# Signal_RX.net
KiCad netlist of a schematic drawn in Altium Designer
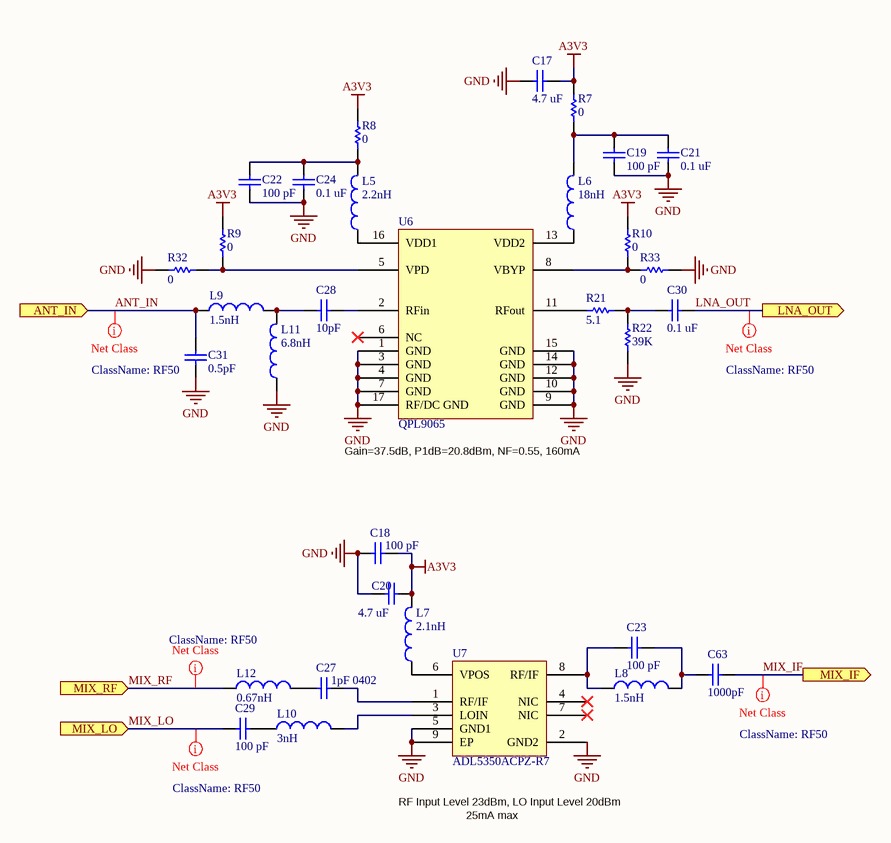
[diagram p0: Signal_RX.SchDoc]

(export (version "E")
  (design (tool "Eeschema 10.0.6"))
  (components
    (comp (ref "C17")
      (value "4.7 uF")
      (footprint "CAPC1608X10L")
      (description "Multilayer Ceramic Capacitors MLCC - SMD/SMT 0603 4.7uF 16volts X5R + - 10%")
      (fields
        (field (name "MANUFACTURER") "Murata Electronics")
        (field (name "MANUFACTURER PART NUMBER") "GRM188R61C475KAAJD")
      )
      (libsource (lib "Componentes_base") (part "GRM188R61C475KAAJD_1"))
    )
    (comp (ref "C18")
      (value "100 pF")
      (footprint "CAPC1005X05L")
      (description "CAP CER 100PF 50V NP0 0402")
      (fields
        (field (name "MANUFACTURER") "Murata Electronics North America")
        (field (name "MANUFACTURER PART NUMBER") "GRM1555C1H101GA01D")
      )
      (libsource (lib "Componentes_base") (part "GRM1555C1H101GA01D"))
    )
    (comp (ref "C19")
      (value "100 pF")
      (footprint "CAPC1005X05L")
      (description "CAP CER 100PF 50V NP0 0402")
      (fields
        (field (name "MANUFACTURER") "Murata Electronics North America")
        (field (name "MANUFACTURER PART NUMBER") "GRM1555C1H101GA01D")
      )
      (libsource (lib "Componentes_base") (part "GRM1555C1H101GA01D"))
    )
    (comp (ref "C20")
      (value "4.7 uF")
      (footprint "CAPC1608X10L")
      (description "Multilayer Ceramic Capacitors MLCC - SMD/SMT 0603 4.7uF 16volts X5R + - 10%")
      (fields
        (field (name "MANUFACTURER") "Murata Electronics")
        (field (name "MANUFACTURER PART NUMBER") "GRM188R61C475KAAJD")
      )
      (libsource (lib "Componentes_base") (part "GRM188R61C475KAAJD"))
    )
    (comp (ref "C21")
      (value "0.1 uF")
      (footprint "CAPC1005X05L")
      (description "CAP CER 0.1UF 16V 10% X7R 0402")
      (fields
        (field (name "MANUFACTURER") "Samsung Electro-Mechanics America, Inc")
        (field (name "MANUFACTURER PART NUMBER") "CL05B104KO5NNNC")
      )
      (libsource (lib "Componentes_base") (part "CL05B104KO5NNNC"))
    )
    (comp (ref "C22")
      (value "100 pF")
      (footprint "CAPC1005X05L")
      (description "CAP CER 100PF 50V NP0 0402")
      (fields
        (field (name "MANUFACTURER") "Murata Electronics North America")
        (field (name "MANUFACTURER PART NUMBER") "GRM1555C1H101GA01D")
      )
      (libsource (lib "Componentes_base") (part "GRM1555C1H101GA01D"))
    )
    (comp (ref "C23")
      (value "100 pF")
      (footprint "CAPC1005X05L")
      (description "CAP CER 100PF 50V NP0 0402")
      (fields
        (field (name "MANUFACTURER") "Murata Electronics North America")
        (field (name "MANUFACTURER PART NUMBER") "GRM1555C1H101GA01D")
      )
      (libsource (lib "Componentes_base") (part "GRM1555C1H101GA01D"))
    )
    (comp (ref "C24")
      (value "0.1 uF")
      (footprint "CAPC1005X05L")
      (description "CAP CER 0.1UF 16V 10% X7R 0402")
      (fields
        (field (name "MANUFACTURER") "Samsung Electro-Mechanics America, Inc")
        (field (name "MANUFACTURER PART NUMBER") "CL05B104KO5NNNC")
      )
      (libsource (lib "Componentes_base") (part "CL05B104KO5NNNC"))
    )
    (comp (ref "C27")
      (value "1pF 0402")
      (footprint "CAPC1005X05L")
      (description "CAP CER 1PF 50V C0G/NP0 0402")
      (libsource (lib "Componentes_base") (part "GRM1555C1H1R0CA01D"))
    )
    (comp (ref "C28")
      (value "10pF")
      (footprint "CAPC1005X05L")
      (description "CAP CER 10PF 50V C0G/NP0 0402")
      (fields
        (field (name "MANUFACTURER") "Murata Electronics North America")
        (field (name "MANUFACTURER PART NUMBER") "GRM1555C1H100JA01D")
      )
      (libsource (lib "Componentes_base") (part "GRM1555C1H100JA01D"))
    )
    (comp (ref "C29")
      (value "100 pF")
      (footprint "CAPC1005X05L")
      (description "CAP CER 100PF 50V NP0 0402")
      (fields
        (field (name "MANUFACTURER") "Murata Electronics North America")
        (field (name "MANUFACTURER PART NUMBER") "GRM1555C1H101GA01D")
      )
      (libsource (lib "Componentes_base") (part "GRM1555C1H101GA01D"))
    )
    (comp (ref "C30")
      (value "0.1 uF")
      (footprint "CAPC1005X05L")
      (description "CAP CER 0.1UF 16V 10% X7R 0402")
      (fields
        (field (name "MANUFACTURER") "Samsung Electro-Mechanics America, Inc")
        (field (name "MANUFACTURER PART NUMBER") "CL05B104KO5NNNC")
      )
      (libsource (lib "Componentes_base") (part "CL05B104KO5NNNC"))
    )
    (comp (ref "C31")
      (value "0.5pF")
      (footprint "CAPC1005X05L")
      (description "CAP CER 0.5PF 50V C0G/NP0 0402")
      (fields
        (field (name "MANUFACTURER") "Murata Electronics North America")
        (field (name "MANUFACTURER PART NUMBER") "GJM1555C1HR50BB01D")
      )
      (libsource (lib "Componentes_base") (part "GJM1555C1HR50BB01D"))
    )
    (comp (ref "C63")
      (value "1000pF")
      (footprint "CAPC1005X05L")
      (description "CAP CER 1000PF 50V C0G/NP0 0402")
      (fields
        (field (name "MANUFACTURER") "Murata Electronics North America")
        (field (name "MANUFACTURER PART NUMBER") "GRM1555C1H102JA01D")
      )
      (libsource (lib "Componentes_base") (part "GRM1555C1H102JA01D"))
    )
    (comp (ref "L5")
      (value "2.2nH")
      (footprint "INDC1005X06L")
      (description "FIXED IND 2.2NH 1A 27 MOHM SMD")
      (fields
        (field (name "MANUFACTURER") "Murata Electronics North America")
        (field (name "MANUFACTURER PART NUMBER") "LQW15AN2N2C10D")
      )
      (libsource (lib "Componentes_base") (part "LQW15AN2N2C10D"))
    )
    (comp (ref "L6")
      (value "18nH")
      (footprint "INDC1811X10L 0603CS")
      (description "COILCRAFT - 0603CS-18NXJLU - INDUCTOR, RF, 18NH, 5%, 3.1GHZ, SMD")
      (libsource (lib "Componentes_base") (part "0603CS-18NXJLU"))
    )
    (comp (ref "L7")
      (value "2.1nH")
      (footprint "INDC0905X05N-0302CS")
      (description "COILCRAFT - 0302CS-2N1XJLU - INDUCTOR, RF, 2.1NH,5%,15.94GHZ, SMD")
      (fields
        (field (name "MANUFACTURER") "COILCRAFT")
        (field (name "MANUFACTURER PART NUMBER") "0302CS-2N1XJLU")
        (field (name "FRECUENCIA AUTORRESONANTE MÍN.") "5.94")
      )
      (libsource (lib "Componentes_base") (part "0302CS-2N1XJLU"))
    )
    (comp (ref "L8")
      (value "1.5nH")
      (footprint "INDC1005X06L")
      (description "FIXED IND 1.5NH 280MA 200 MOHM")
      (fields
        (field (name "MANUFACTURER") "Murata Electronics North America")
        (field (name "MANUFACTURER PART NUMBER") "LQP15MN1N5B02D")
      )
      (libsource (lib "Componentes_base") (part "LQP15MN1N5B02D"))
    )
    (comp (ref "L9")
      (value "1.5nH")
      (footprint "INDC1005X06L")
      (description "FIXED IND 1.5NH 280MA 200 MOHM")
      (fields
        (field (name "MANUFACTURER") "Murata Electronics North America")
        (field (name "MANUFACTURER PART NUMBER") "LQP15MN1N5B02D")
      )
      (libsource (lib "Componentes_base") (part "LQP15MN1N5B02D"))
    )
    (comp (ref "L10")
      (value "3nH")
      (footprint "INDC1005X06L")
      (description "FIXED IND 3NH 190MA 400 MOHM SMD")
      (fields
        (field (name "MANUFACTURER") "Murata Electronics North America")
        (field (name "MANUFACTURER PART NUMBER") "LQP15MN3N0B02D")
      )
      (libsource (lib "Componentes_base") (part "LQP15MN3N0B02D"))
    )
    (comp (ref "L11")
      (value "6.8nH")
      (footprint "INDC1005X06L")
      (description "FIXED IND 6.8NH 600MA 240 MOHM")
      (fields
        (field (name "MANUFACTURER") "Murata Electronics North America")
        (field (name "MANUFACTURER PART NUMBER") "LQG15HS6N8J02D")
      )
      (libsource (lib "Componentes_base") (part "LQG15HS6N8J02D"))
    )
    (comp (ref "L12")
      (value "0.67nH")
      (footprint "INDC0905X05N-0302CS")
      (description "COILCRAFT - 0302CS-N67XKLU - INDUCTOR, RF, 0.67NH, 10%,26GHZ, SMD")
      (fields
        (field (name "MANUFACTURER") "COILCRAFT")
        (field (name "MANUFACTURER PART NUMBER") "0302CS-N67XKLU")
        (field (name "FRECUENCIA AUTORRESONANTE MÍN.") "26")
      )
      (libsource (lib "Componentes_base") (part "0302CS-N67XKLU"))
    )
    (comp (ref "R7")
      (value "0")
      (footprint "RESC1005X04L")
      (description "RES 0.0 OHM 1/16W JUMP 0402")
      (fields
        (field (name "MANUFACTURER") "Samsung Electro-Mechanics America, Inc")
        (field (name "MANUFACTURER PART NUMBER") "RC1005J000CS")
      )
      (libsource (lib "Componentes_base") (part "RC1005J000CS"))
    )
    (comp (ref "R8")
      (value "0")
      (footprint "RESC1005X04L")
      (description "RES 0.0 OHM 1/16W JUMP 0402")
      (fields
        (field (name "MANUFACTURER") "Samsung Electro-Mechanics America, Inc")
        (field (name "MANUFACTURER PART NUMBER") "RC1005J000CS")
      )
      (libsource (lib "Componentes_base") (part "RC1005J000CS"))
    )
    (comp (ref "R9")
      (value "0")
      (footprint "RESC1005X04L")
      (description "RES 0.0 OHM 1/16W JUMP 0402")
      (fields
        (field (name "MANUFACTURER") "Samsung Electro-Mechanics America, Inc")
        (field (name "MANUFACTURER PART NUMBER") "RC1005J000CS")
      )
      (libsource (lib "Componentes_base") (part "RC1005J000CS"))
    )
    (comp (ref "R10")
      (value "0")
      (footprint "RESC1005X04L")
      (description "RES 0.0 OHM 1/16W JUMP 0402")
      (fields
        (field (name "MANUFACTURER") "Samsung Electro-Mechanics America, Inc")
        (field (name "MANUFACTURER PART NUMBER") "RC1005J000CS")
      )
      (libsource (lib "Componentes_base") (part "RC1005J000CS"))
    )
    (comp (ref "R21")
      (value "5.1")
      (footprint "RESC1005X04L")
      (description "RES SMD 5.1 OHM 1% 1/16W 0402")
      (fields
        (field (name "MANUFACTURER") "Samsung Electro-Mechanics America, Inc.")
        (field (name "MANUFACTURER PART NUMBER") "RC1005F5R1CS")
      )
      (libsource (lib "Componentes_base") (part "RC1005F5R1CS"))
    )
    (comp (ref "R22")
      (value "39K")
      (footprint "RESC1005X04L")
      (description "RES SMD 39K OHM 1% 1/16W 0402")
      (fields
        (field (name "MANUFACTURER") "Yageo")
        (field (name "MANUFACTURER PART NUMBER") "RC0402FR-0739KL")
      )
      (libsource (lib "Componentes_base") (part "RC0402FR-0739KL"))
    )
    (comp (ref "R32")
      (value "0")
      (footprint "RESC1005X04L")
      (description "RES 0.0 OHM 1/16W JUMP 0402")
      (fields
        (field (name "MANUFACTURER") "Samsung Electro-Mechanics America, Inc")
        (field (name "MANUFACTURER PART NUMBER") "RC1005J000CS")
      )
      (libsource (lib "Componentes_base") (part "RC1005J000CS"))
    )
    (comp (ref "R33")
      (value "0")
      (footprint "RESC1005X04L")
      (description "RES 0.0 OHM 1/16W JUMP 0402")
      (fields
        (field (name "MANUFACTURER") "Samsung Electro-Mechanics America, Inc")
        (field (name "MANUFACTURER PART NUMBER") "RC1005J000CS")
      )
      (libsource (lib "Componentes_base") (part "RC1005J000CS"))
    )
    (comp (ref "U6")
      (value "QPL9065")
      (footprint "QFN50P350X350X86_HS-17N-qorvo")
      (fields
        (field (name "MANUFACTURER PART NUMBER") "772-QPL9065TR13")
        (field (name "MANUFACTURER") "COILCRAFT")
        (field (name "FRECUENCIA AUTORRESONANTE MÍN.") "3.1")
      )
      (libsource (lib "Componentes_base") (part "QPL9065"))
    )
    (comp (ref "U7")
      (value "ADL5350ACPZ-R7")
      (footprint "SON50P200X80_HS-9N")
      (description "IC MIXER 750MHZ-4GHZ 8LFCSP")
      (fields (field (name "MANUFACTURER") "Analog Devices Inc."))
      (libsource (lib "Componentes_base") (part "ADL5350ACPZ-R7"))
    )
  )
  (nets
    (net (code "1") (name "/ANT_IN") (class "Default")
      (node (ref "C31") (pin "2") (pinfunction "2_2") (pintype "passive"))
      (node (ref "L9") (pin "1") (pinfunction "1_1") (pintype "passive"))
    )
    (net (code "2") (name "/LNA_OUT") (class "Default")
      (node (ref "C30") (pin "1") (pinfunction "1_1") (pintype "passive"))
    )
    (net (code "3") (name "/MIX_IF") (class "Default")
      (node (ref "C63") (pin "2") (pinfunction "2_2") (pintype "passive"))
    )
    (net (code "4") (name "/MIX_LO") (class "Default")
      (node (ref "C29") (pin "1") (pinfunction "1_1") (pintype "passive"))
    )
    (net (code "5") (name "/MIX_RF") (class "Default")
      (node (ref "L12") (pin "1") (pinfunction "1_1") (pintype "passive"))
    )
    (net (code "6") (name "A3V3") (class "Default")
      (node (ref "C17") (pin "2") (pinfunction "2_2") (pintype "passive"))
      (node (ref "C18") (pin "2") (pinfunction "2_2") (pintype "passive"))
      (node (ref "C20") (pin "1") (pinfunction "1_1") (pintype "passive"))
      (node (ref "L7") (pin "2") (pinfunction "2_2") (pintype "passive"))
      (node (ref "R10") (pin "1") (pinfunction "1_1") (pintype "passive"))
      (node (ref "R7") (pin "2") (pinfunction "2_2") (pintype "passive"))
      (node (ref "R8") (pin "1") (pinfunction "1_1") (pintype "passive"))
      (node (ref "R9") (pin "2") (pinfunction "2_2") (pintype "passive"))
    )
    (net (code "7") (name "GND") (class "Default")
      (node (ref "C17") (pin "1") (pinfunction "1_1") (pintype "passive"))
      (node (ref "C18") (pin "1") (pinfunction "1_1") (pintype "passive"))
      (node (ref "C19") (pin "2") (pinfunction "2_2") (pintype "passive"))
      (node (ref "C20") (pin "2") (pinfunction "2_2") (pintype "passive"))
      (node (ref "C21") (pin "1") (pinfunction "1_1") (pintype "passive"))
      (node (ref "C22") (pin "2") (pinfunction "2_2") (pintype "passive"))
      (node (ref "C24") (pin "1") (pinfunction "1_1") (pintype "passive"))
      (node (ref "C31") (pin "1") (pinfunction "1_1") (pintype "passive"))
      (node (ref "L11") (pin "1") (pinfunction "1_1") (pintype "passive"))
      (node (ref "R22") (pin "1") (pinfunction "1_1") (pintype "passive"))
      (node (ref "R32") (pin "2") (pinfunction "2_2") (pintype "passive"))
      (node (ref "R33") (pin "1") (pinfunction "1_1") (pintype "passive"))
      (node (ref "U6") (pin "1") (pinfunction "GND_1") (pintype "passive"))
      (node (ref "U6") (pin "10") (pinfunction "GND_10") (pintype "passive"))
      (node (ref "U6") (pin "12") (pinfunction "GND_12") (pintype "passive"))
      (node (ref "U6") (pin "14") (pinfunction "GND_14") (pintype "passive"))
      (node (ref "U6") (pin "15") (pinfunction "GND_15") (pintype "passive"))
      (node (ref "U6") (pin "17") (pinfunction "RF/DC_GND_17") (pintype "passive"))
      (node (ref "U6") (pin "3") (pinfunction "GND_3") (pintype "passive"))
      (node (ref "U6") (pin "4") (pinfunction "GND_4") (pintype "passive"))
      (node (ref "U6") (pin "7") (pinfunction "GND_7") (pintype "passive"))
      (node (ref "U6") (pin "9") (pinfunction "GND_9") (pintype "passive"))
      (node (ref "U7") (pin "2") (pinfunction "GND2_2") (pintype "passive"))
      (node (ref "U7") (pin "5") (pinfunction "GND1_5") (pintype "passive"))
      (node (ref "U7") (pin "9") (pinfunction "EP_9") (pintype "passive"))
    )
    (net (code "8") (name "Net-(C19-Pad1)") (class "Default")
      (node (ref "C19") (pin "1") (pinfunction "1_1") (pintype "passive"))
      (node (ref "C21") (pin "2") (pinfunction "2_2") (pintype "passive"))
      (node (ref "L6") (pin "2") (pinfunction "2_2") (pintype "passive"))
      (node (ref "R7") (pin "1") (pinfunction "1_1") (pintype "passive"))
    )
    (net (code "9") (name "Net-(C22-Pad1)") (class "Default")
      (node (ref "C22") (pin "1") (pinfunction "1_1") (pintype "passive"))
      (node (ref "C24") (pin "2") (pinfunction "2_2") (pintype "passive"))
      (node (ref "L5") (pin "2") (pinfunction "2_2") (pintype "passive"))
      (node (ref "R8") (pin "2") (pinfunction "2_2") (pintype "passive"))
    )
    (net (code "10") (name "Net-(C23-Pad1)") (class "Default")
      (node (ref "C23") (pin "1") (pinfunction "1_1") (pintype "passive"))
      (node (ref "L8") (pin "1") (pinfunction "1_1") (pintype "passive"))
      (node (ref "U7") (pin "8") (pinfunction "RF/IF_8") (pintype "passive"))
    )
    (net (code "11") (name "Net-(C23-Pad2)") (class "Default")
      (node (ref "C23") (pin "2") (pinfunction "2_2") (pintype "passive"))
      (node (ref "C63") (pin "1") (pinfunction "1_1") (pintype "passive"))
      (node (ref "L8") (pin "2") (pinfunction "2_2") (pintype "passive"))
    )
    (net (code "12") (name "Net-(C27-Pad1)") (class "Default")
      (node (ref "C27") (pin "1") (pinfunction "1_1") (pintype "passive"))
      (node (ref "L12") (pin "2") (pinfunction "2_2") (pintype "passive"))
    )
    (net (code "13") (name "Net-(C27-Pad2)") (class "Default")
      (node (ref "C27") (pin "2") (pinfunction "2_2") (pintype "passive"))
      (node (ref "U7") (pin "1") (pinfunction "RF/IF_1") (pintype "passive"))
    )
    (net (code "14") (name "Net-(C28-Pad1)") (class "Default")
      (node (ref "C28") (pin "1") (pinfunction "1_1") (pintype "passive"))
      (node (ref "L11") (pin "2") (pinfunction "2_2") (pintype "passive"))
      (node (ref "L9") (pin "2") (pinfunction "2_2") (pintype "passive"))
    )
    (net (code "15") (name "Net-(C29-Pad2)") (class "Default")
      (node (ref "C29") (pin "2") (pinfunction "2_2") (pintype "passive"))
      (node (ref "L10") (pin "1") (pinfunction "1_1") (pintype "passive"))
    )
    (net (code "16") (name "Net-(C30-Pad2)") (class "Default")
      (node (ref "C30") (pin "2") (pinfunction "2_2") (pintype "passive"))
      (node (ref "R21") (pin "2") (pinfunction "2_2") (pintype "passive"))
      (node (ref "R22") (pin "2") (pinfunction "2_2") (pintype "passive"))
    )
    (net (code "17") (name "Net-(U6-RFin)") (class "Default")
      (node (ref "C28") (pin "2") (pinfunction "2_2") (pintype "passive"))
      (node (ref "U6") (pin "2") (pinfunction "RFin_2") (pintype "passive"))
    )
    (net (code "18") (name "Net-(U6-RFout)") (class "Default")
      (node (ref "R21") (pin "1") (pinfunction "1_1") (pintype "passive"))
      (node (ref "U6") (pin "11") (pinfunction "RFout_11") (pintype "passive"))
    )
    (net (code "19") (name "Net-(U6-VBYP)") (class "Default")
      (node (ref "R10") (pin "2") (pinfunction "2_2") (pintype "passive"))
      (node (ref "R33") (pin "2") (pinfunction "2_2") (pintype "passive"))
      (node (ref "U6") (pin "8") (pinfunction "VBYP_8") (pintype "passive"))
    )
    (net (code "20") (name "Net-(U6-VDD1)") (class "Default")
      (node (ref "L5") (pin "1") (pinfunction "1_1") (pintype "passive"))
      (node (ref "U6") (pin "16") (pinfunction "VDD1_16") (pintype "passive"))
    )
    (net (code "21") (name "Net-(U6-VDD2)") (class "Default")
      (node (ref "L6") (pin "1") (pinfunction "1_1") (pintype "passive"))
      (node (ref "U6") (pin "13") (pinfunction "VDD2_13") (pintype "passive"))
    )
    (net (code "22") (name "Net-(U6-VPD)") (class "Default")
      (node (ref "R32") (pin "1") (pinfunction "1_1") (pintype "passive"))
      (node (ref "R9") (pin "1") (pinfunction "1_1") (pintype "passive"))
      (node (ref "U6") (pin "5") (pinfunction "VPD_5") (pintype "passive"))
    )
    (net (code "23") (name "Net-(U7-LOIN)") (class "Default")
      (node (ref "L10") (pin "2") (pinfunction "2_2") (pintype "passive"))
      (node (ref "U7") (pin "3") (pinfunction "LOIN_3") (pintype "passive"))
    )
    (net (code "24") (name "Net-(U7-VPOS)") (class "Default")
      (node (ref "L7") (pin "1") (pinfunction "1_1") (pintype "passive"))
      (node (ref "U7") (pin "6") (pinfunction "VPOS_6") (pintype "passive"))
    )
    (net (code "25") (name "unconnected-(U6-NC-Pad6)") (class "Default")
      (node (ref "U6") (pin "6") (pinfunction "NC_6") (pintype "passive+no_connect"))
    )
    (net (code "26") (name "unconnected-(U7-NIC-Pad4)") (class "Default")
      (node (ref "U7") (pin "4") (pinfunction "NIC_4") (pintype "passive+no_connect"))
    )
    (net (code "27") (name "unconnected-(U7-NIC-Pad7)") (class "Default")
      (node (ref "U7") (pin "7") (pinfunction "NIC_7") (pintype "passive+no_connect"))
    )
  )
)
